# Input_Connectors_and_Sensors.net
KiCad netlist of a schematic drawn in Altium Designer
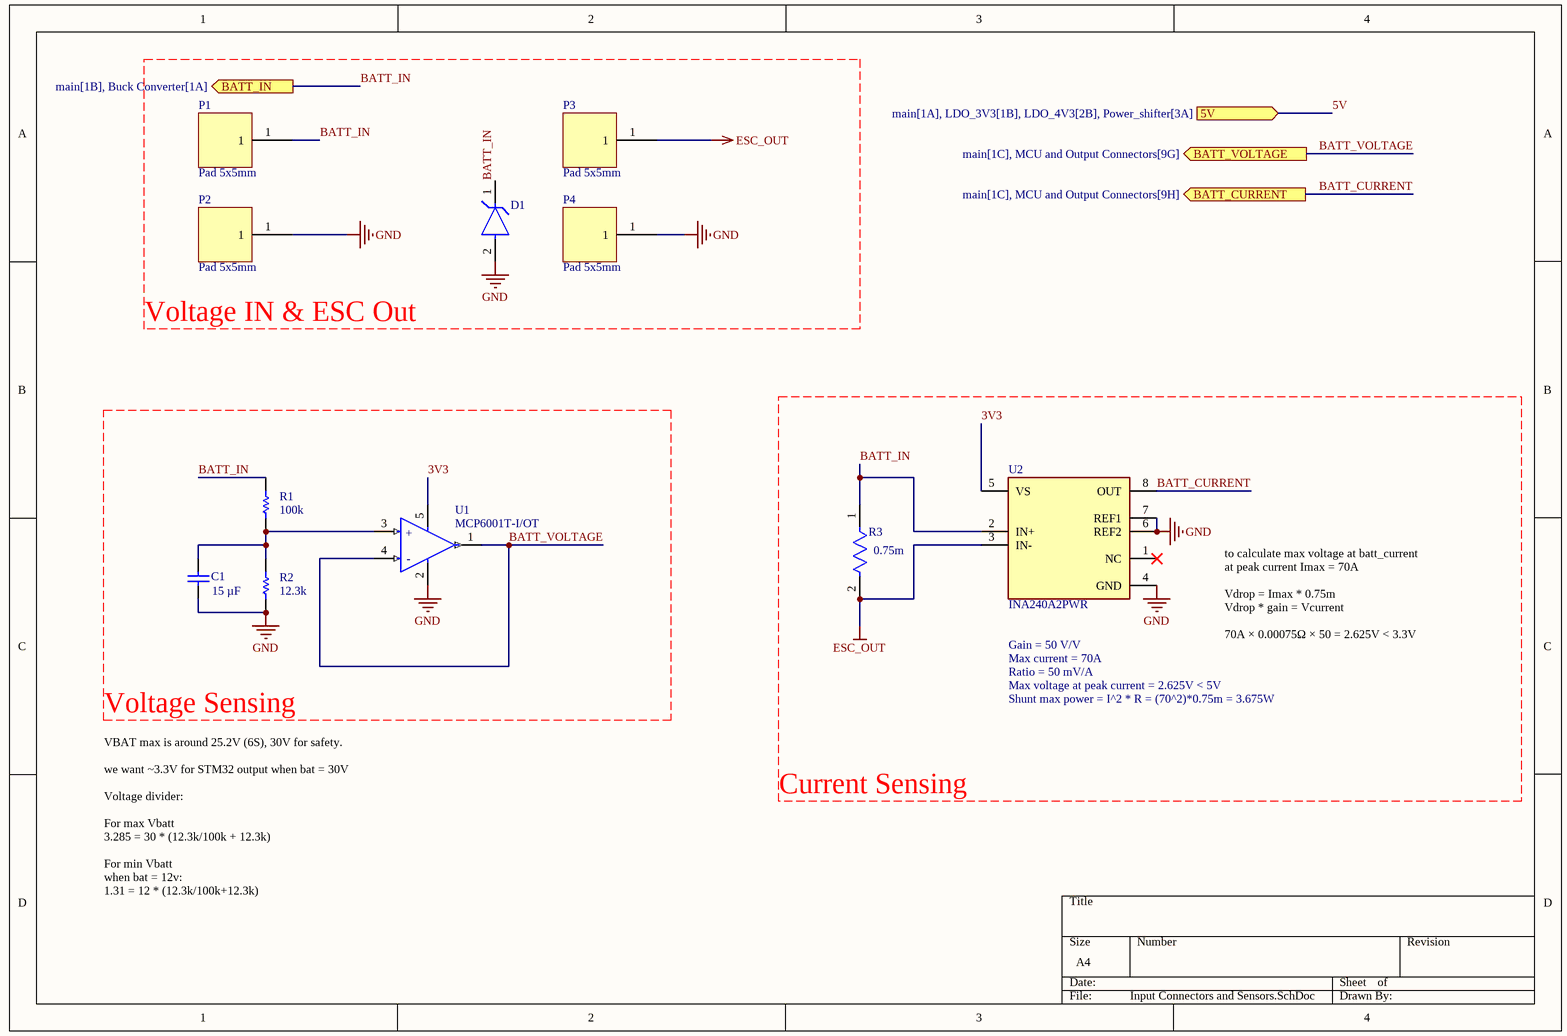
[diagram p0: Input Connectors and Sensors.SchDoc]

(export (version "E")
  (design (tool "Eeschema 10.0.6"))
  (components
    (comp (ref "C1")
      (value "15 µF")
      (footprint "0603_CAPC1608L")
      (description "Capacitor (Semiconductor SIM Model)")
      (fields (field (name "Comment") "Cap Semi") (field (name "PUBLISHER") "Altium Limited"))
      (libsource (lib "MiscDev 3") (part "Cap Semi"))
    )
    (comp (ref "D1")
      (value "1.5SMC30AHE3_A/H")
      (footprint "FP-SMC-MFG")
      (description "TVS DIODE 25.6VWM 41.4VC SMC")
      (libsource (lib "Altium Content Vault") (part "d9da4cfb8af32e832502365dfa3d88e"))
    )
    (comp (ref "P1")
      (value "Pad 5x5mm")
      (footprint "PAD 5X5MM")
      (libsource (lib "Matsean Library") (part "Pad 5x5mm"))
    )
    (comp (ref "P2")
      (value "Pad 5x5mm")
      (footprint "PAD 5X5MM")
      (libsource (lib "Matsean Library") (part "Pad 5x5mm"))
    )
    (comp (ref "P3")
      (value "Pad 5x5mm")
      (footprint "PAD 5X5MM")
      (libsource (lib "Matsean Library") (part "Pad 5x5mm"))
    )
    (comp (ref "P4")
      (value "Pad 5x5mm")
      (footprint "PAD 5X5MM")
      (libsource (lib "Matsean Library") (part "Pad 5x5mm"))
    )
    (comp (ref "R1")
      (value "100k")
      (footprint "0402_RESC1005L")
      (description "Semiconductor Resistor")
      (fields (field (name "Comment") "Res Semi") (field (name "PUBLISHER") "Altium Limited"))
      (libsource (lib "MiscDev 3") (part "Res Semi"))
    )
    (comp (ref "R2")
      (value "12.3k")
      (footprint "0402_RESC1005L")
      (description "Semiconductor Resistor")
      (fields (field (name "Comment") "Res Semi") (field (name "PUBLISHER") "Altium Limited"))
      (libsource (lib "MiscDev 3") (part "Res Semi"))
    )
    (comp (ref "R3")
      (value "SCMM2512S5-R001F")
      (footprint "FP-AC2512-MFG")
      (description "RES 0.001 OHM 1% 5W 2512")
      (fields
        (field (name "RESISTANCE") "0.75m")
        (field (name "TOLERANCE") "0.05")
        (field (name "MANUFACTURER PART NUMBER") "AC2512JK-072K4L")
      )
      (libsource (lib "Altium Content Vault") (part "1029c3af85768c4190bb7ad29bc67b5"))
    )
    (comp (ref "U1")
      (value "MCP6001T-I/OT")
      (footprint "FP-C04-091-OT-IPC_A")
      (description "IC OPAMP GP 1 CIRCUIT SOT23-5")
      (fields (field (name "VOLTAGE") "6V"))
      (libsource (lib "Altium Content Vault") (part "c8a8c153b9e84e05c1733c8ea85bdd9"))
    )
    (comp (ref "U2")
      (value "INA240A2PWR")
      (footprint "FP-PW0008A-MFG")
      (description "IC AMP CURRENT SENSE 8-TSSOP")
      (fields
        (field (name "OCTOPART") "https://octopart.com/ina240a2pwr-texas+instruments-75431049")
        (field (name "MANUFACTURER") "Texas Instruments")
      )
      (libsource (lib "Altium Content Vault") (part "98c6b1d0971071ba4d7dac1d4a4ea92"))
    )
  )
  (nets
    (net (code "1") (name "/3V3") (class "Default")
      (node (ref "U1") (pin "5") (pinfunction "VDD_5") (pintype "power_in"))
      (node (ref "U2") (pin "5") (pinfunction "VS_5") (pintype "power_in"))
    )
    (net (code "3") (name "/BATT_CURRENT") (class "Default")
      (node (ref "U2") (pin "8") (pinfunction "OUT_8") (pintype "passive"))
    )
    (net (code "4") (name "/BATT_IN") (class "Default")
      (node (ref "D1") (pin "1") (pinfunction "C_1") (pintype "passive"))
      (node (ref "P1") (pin "1") (pinfunction "1_1") (pintype "passive"))
      (node (ref "R1") (pin "2") (pinfunction "2_2") (pintype "passive"))
      (node (ref "R3") (pin "1") (pinfunction "1_1") (pintype "passive"))
      (node (ref "U2") (pin "2") (pinfunction "IN+_2") (pintype "tri_state"))
    )
    (net (code "5") (name "/BATT_VOLTAGE") (class "Default")
      (node (ref "U1") (pin "1") (pinfunction "VOUT_1") (pintype "output"))
      (node (ref "U1") (pin "4") (pinfunction "VIN-_4") (pintype "input"))
    )
    (net (code "6") (name "ESC_OUT") (class "Default")
      (node (ref "P3") (pin "1") (pinfunction "1_1") (pintype "passive"))
      (node (ref "R3") (pin "2") (pinfunction "2_2") (pintype "passive"))
      (node (ref "U2") (pin "3") (pinfunction "IN-_3") (pintype "tri_state"))
    )
    (net (code "7") (name "GND") (class "Default")
      (node (ref "C1") (pin "1") (pinfunction "1_1") (pintype "passive"))
      (node (ref "D1") (pin "2") (pinfunction "A_2") (pintype "passive"))
      (node (ref "P2") (pin "1") (pinfunction "1_1") (pintype "passive"))
      (node (ref "P4") (pin "1") (pinfunction "1_1") (pintype "passive"))
      (node (ref "R2") (pin "1") (pinfunction "1_1") (pintype "passive"))
      (node (ref "U1") (pin "2") (pinfunction "VSS_2") (pintype "power_in"))
      (node (ref "U2") (pin "4") (pinfunction "GND_4") (pintype "power_in"))
      (node (ref "U2") (pin "6") (pinfunction "REF2_6") (pintype "passive"))
      (node (ref "U2") (pin "7") (pinfunction "REF1_7") (pintype "passive"))
    )
    (net (code "8") (name "Net-(U1-VIN+)") (class "Default")
      (node (ref "C1") (pin "2") (pinfunction "2_2") (pintype "passive"))
      (node (ref "R1") (pin "1") (pinfunction "1_1") (pintype "passive"))
      (node (ref "R2") (pin "2") (pinfunction "2_2") (pintype "passive"))
      (node (ref "U1") (pin "3") (pinfunction "VIN+_3") (pintype "input"))
    )
    (net (code "9") (name "unconnected-(U2-NC-Pad1)") (class "Default")
      (node (ref "U2") (pin "1") (pinfunction "NC_1") (pintype "passive+no_connect"))
    )
  )
)
